# sensors_actuators_shieldv1_1.net
KiCad netlist of a schematic drawn in EAGLE
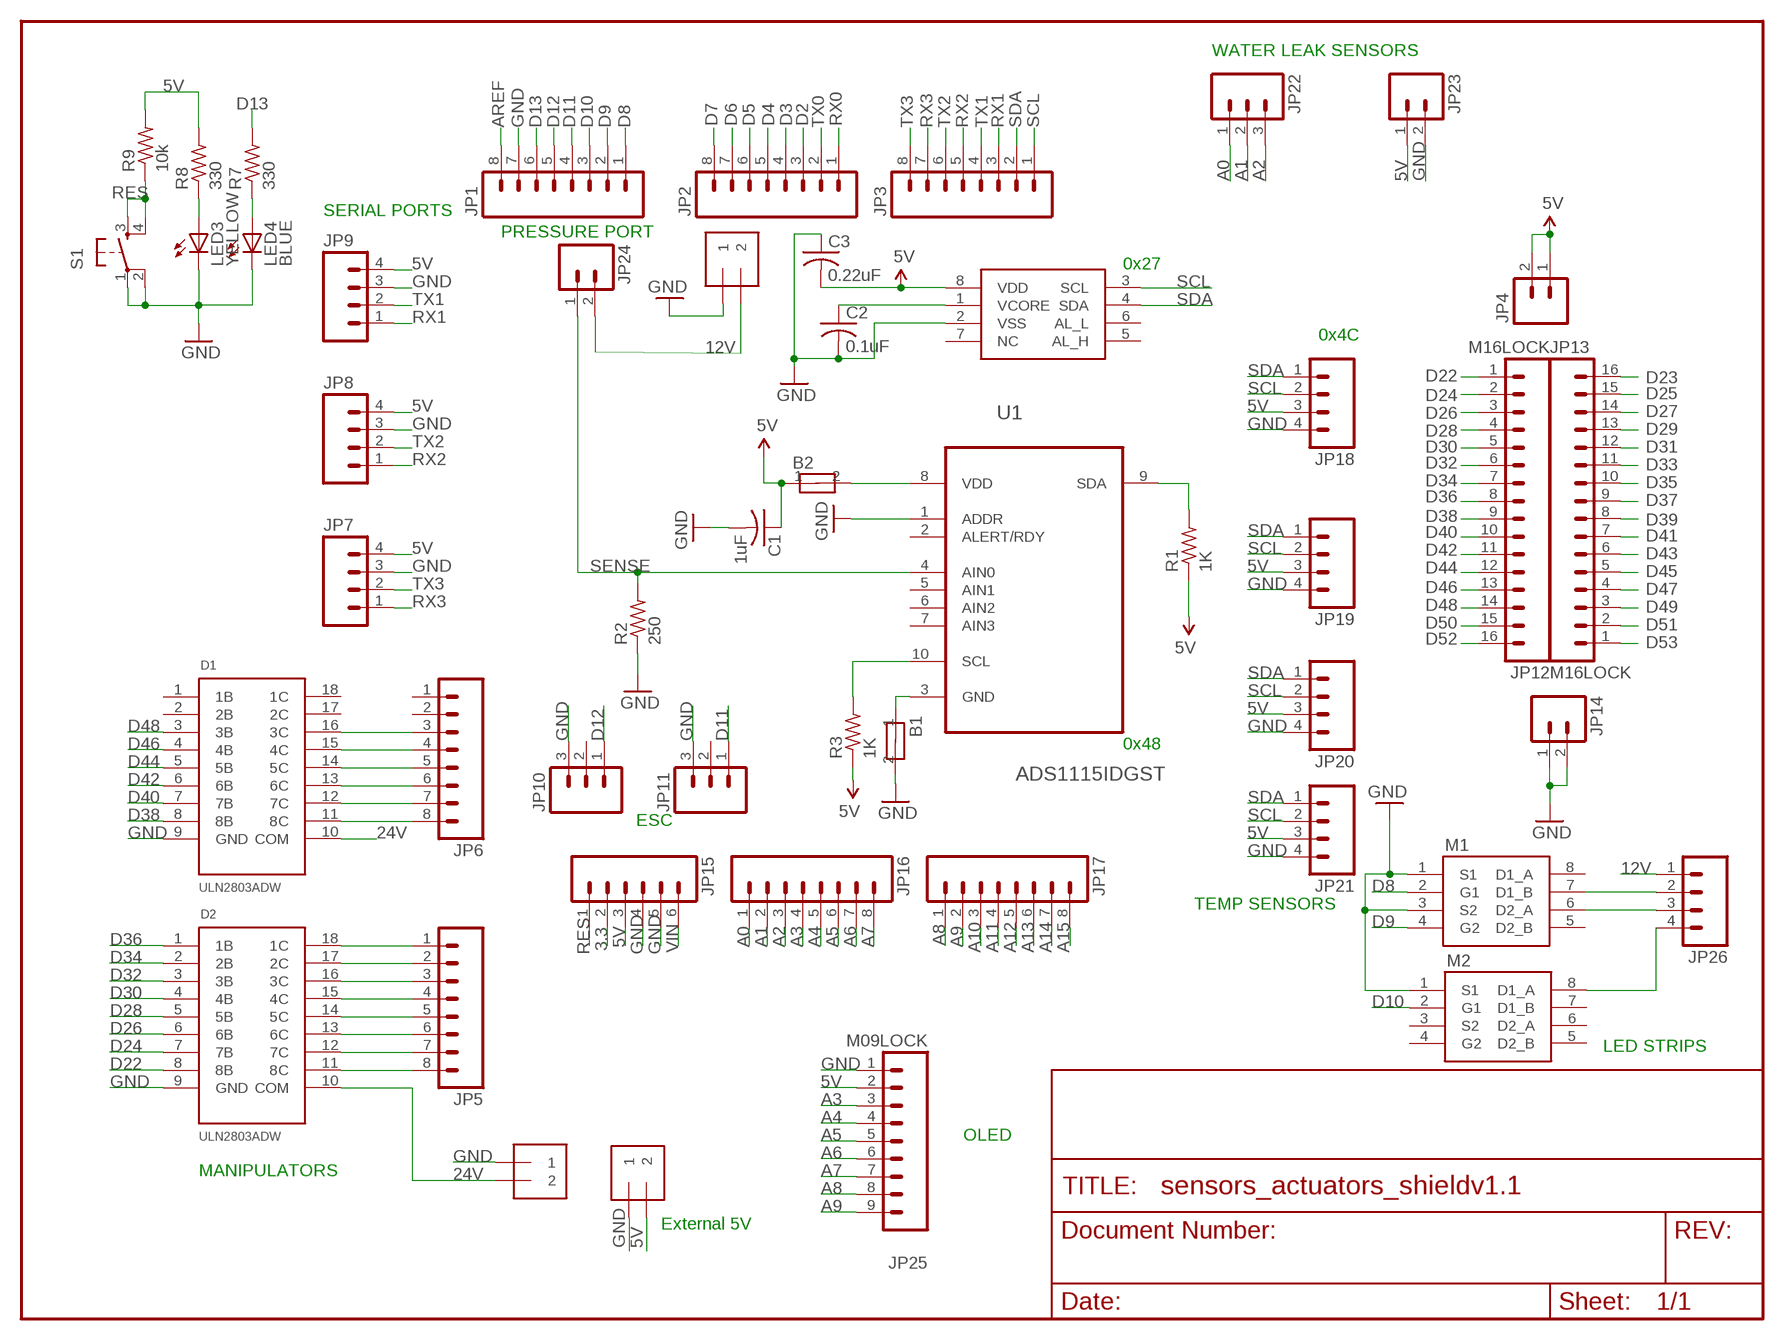
[diagram p0: schematic, sheet 1]

(export (version "E")
  (design (tool "Eeschema 10.0.6"))
  (components
    (comp (ref "B1")
      (value "MMZ2012Y152B0.4OHM,500MA")
      (footprint "eagle-import:0805")
      (fields (field (name "MPN") "MMZ2012Y152B"))
      (libsource (lib "eagle-import") (part "MMZ2012Y152B0.4OHM,500MA"))
    )
    (comp (ref "B2")
      (value "MMZ2012Y152B0.4OHM,500MA")
      (footprint "eagle-import:0805")
      (fields (field (name "MPN") "MMZ2012Y152B"))
      (libsource (lib "eagle-import") (part "MMZ2012Y152B0.4OHM,500MA"))
    )
    (comp (ref "C1")
      (value "1uF")
      (footprint "eagle-import:C0805")
      (fields (field (name "MF") "KEMET") (field (name "MPN") "C0805C105M4RACTU"))
      (libsource (lib "eagle-import") (part "C-USC0805"))
    )
    (comp (ref "C2")
      (value "0.1uF")
      (footprint "eagle-import:C0805")
      (fields (field (name "MPN") "08055C104K4Z2A"))
      (libsource (lib "eagle-import") (part "C-USC0805"))
    )
    (comp (ref "C3")
      (value "0.22uF")
      (footprint "eagle-import:C0805")
      (fields (field (name "MPN") "CGA4J2X8R1E224K125AA"))
      (libsource (lib "eagle-import") (part "C-USC0805"))
    )
    (comp (ref "D1")
      (value "ULN2803ADW")
      (footprint "eagle-import:SOIC")
      (fields (field (name "MF") "TEXAS INSTRUMENTS"))
      (libsource (lib "eagle-import") (part "ULN2803ADW"))
    )
    (comp (ref "D2")
      (value "ULN2803ADW")
      (footprint "eagle-import:SOIC")
      (fields (field (name "MF") "TEXAS INSTRUMENTS"))
      (libsource (lib "eagle-import") (part "ULN2803ADW"))
    )
    (comp (ref "J1")
      (value "1X2-3.5MM")
      (footprint "eagle-import:1X2-3.5MM")
      (fields (field (name "MPN") "691103110002"))
      (libsource (lib "eagle-import") (part "1X2-3.5MM"))
    )
    (comp (ref "J2")
      (value "1X2-3.5MM")
      (footprint "eagle-import:1X2-3.5MM")
      (fields (field (name "MPN") "691103110002"))
      (libsource (lib "eagle-import") (part "1X2-3.5MM"))
    )
    (comp (ref "J3")
      (value "1X2-3.5MM")
      (footprint "eagle-import:1X2-3.5MM")
      (fields (field (name "MPN") "691103110002"))
      (libsource (lib "eagle-import") (part "1X2-3.5MM"))
    )
    (comp (ref "JP1")
      (value "M08LOCK")
      (footprint "eagle-import:1X08_LOCK")
      (libsource (lib "eagle-import") (part "M08LOCK"))
    )
    (comp (ref "JP2")
      (value "M08LOCK")
      (footprint "eagle-import:1X08_LOCK")
      (libsource (lib "eagle-import") (part "M08LOCK"))
    )
    (comp (ref "JP3")
      (value "M08LOCK")
      (footprint "eagle-import:1X08_LOCK")
      (libsource (lib "eagle-import") (part "M08LOCK"))
    )
    (comp (ref "JP4")
      (value "M02LOCK")
      (footprint "eagle-import:1X02_LOCK")
      (libsource (lib "eagle-import") (part "M02LOCK"))
    )
    (comp (ref "JP5")
      (value "M08LOCK")
      (footprint "eagle-import:1X08_LOCK")
      (libsource (lib "eagle-import") (part "M08LOCK"))
    )
    (comp (ref "JP6")
      (value "M08LOCK")
      (footprint "eagle-import:1X08_LOCK")
      (libsource (lib "eagle-import") (part "M08LOCK"))
    )
    (comp (ref "JP7")
      (value "M04LOCK")
      (footprint "eagle-import:1X04_LOCK")
      (libsource (lib "eagle-import") (part "M04LOCK"))
    )
    (comp (ref "JP8")
      (value "M04LOCK")
      (footprint "eagle-import:1X04_LOCK")
      (libsource (lib "eagle-import") (part "M04LOCK"))
    )
    (comp (ref "JP9")
      (value "M04LOCK")
      (footprint "eagle-import:1X04_LOCK")
      (libsource (lib "eagle-import") (part "M04LOCK"))
    )
    (comp (ref "JP10")
      (value "M03LOCK")
      (footprint "eagle-import:1X03_LOCK")
      (libsource (lib "eagle-import") (part "M03LOCK"))
    )
    (comp (ref "JP11")
      (value "M03LOCK")
      (footprint "eagle-import:1X03_LOCK")
      (libsource (lib "eagle-import") (part "M03LOCK"))
    )
    (comp (ref "JP12")
      (value "M16LOCK")
      (footprint "eagle-import:1X16_LOCK")
      (libsource (lib "eagle-import") (part "M16LOCK"))
    )
    (comp (ref "JP13")
      (value "M16LOCK")
      (footprint "eagle-import:1X16_LOCK")
      (libsource (lib "eagle-import") (part "M16LOCK"))
    )
    (comp (ref "JP14")
      (value "M02LOCK")
      (footprint "eagle-import:1X02_LOCK")
      (libsource (lib "eagle-import") (part "M02LOCK"))
    )
    (comp (ref "JP15")
      (value "M06LOCK")
      (footprint "eagle-import:1X06_LOCK")
      (libsource (lib "eagle-import") (part "M06LOCK"))
    )
    (comp (ref "JP16")
      (value "M08LOCK")
      (footprint "eagle-import:1X08_LOCK")
      (libsource (lib "eagle-import") (part "M08LOCK"))
    )
    (comp (ref "JP17")
      (value "M08LOCK")
      (footprint "eagle-import:1X08_LOCK")
      (libsource (lib "eagle-import") (part "M08LOCK"))
    )
    (comp (ref "JP18")
      (value "M04LOCK")
      (footprint "eagle-import:1X04_LOCK")
      (libsource (lib "eagle-import") (part "M04LOCK"))
    )
    (comp (ref "JP19")
      (value "M04LOCK")
      (footprint "eagle-import:1X04_LOCK")
      (libsource (lib "eagle-import") (part "M04LOCK"))
    )
    (comp (ref "JP20")
      (value "M04LOCK")
      (footprint "eagle-import:1X04_LOCK")
      (libsource (lib "eagle-import") (part "M04LOCK"))
    )
    (comp (ref "JP21")
      (value "M04LOCK")
      (footprint "eagle-import:1X04_LOCK")
      (libsource (lib "eagle-import") (part "M04LOCK"))
    )
    (comp (ref "JP22")
      (value "M03LOCK")
      (footprint "eagle-import:1X03_LOCK")
      (libsource (lib "eagle-import") (part "M03LOCK"))
    )
    (comp (ref "JP23")
      (value "M02LOCK")
      (footprint "eagle-import:1X02_LOCK")
      (libsource (lib "eagle-import") (part "M02LOCK"))
    )
    (comp (ref "JP24")
      (value "M02LOCK")
      (footprint "eagle-import:1X02_LOCK")
      (libsource (lib "eagle-import") (part "M02LOCK"))
    )
    (comp (ref "JP25")
      (value "M09LOCK")
      (footprint "eagle-import:1X09_LOCK")
      (libsource (lib "eagle-import") (part "M09LOCK"))
    )
    (comp (ref "JP26")
      (value "M04LOCK")
      (footprint "eagle-import:1X04_LOCK")
      (libsource (lib "eagle-import") (part "M04LOCK"))
    )
    (comp (ref "LED3")
      (value "YELLOW")
      (footprint "eagle-import:CHIPLED_0805")
      (fields (field (name "MPN") "KP-2012SYCK-J3"))
      (libsource (lib "eagle-import") (part "LEDCHIPLED_0805"))
    )
    (comp (ref "LED4")
      (value "BLUE")
      (footprint "eagle-import:CHIPLED_0805")
      (fields (field (name "MPN") "150080BS75000"))
      (libsource (lib "eagle-import") (part "LEDCHIPLED_0805"))
    )
    (comp (ref "M1")
      (value "IRF7910PBF")
      (footprint "eagle-import:SO-8")
      (libsource (lib "eagle-import") (part "IRF7910PBF"))
    )
    (comp (ref "M2")
      (value "IRF7910PBF")
      (footprint "eagle-import:SO-8")
      (libsource (lib "eagle-import") (part "IRF7910PBF"))
    )
    (comp (ref "R1")
      (value "1K")
      (footprint "eagle-import:M0805")
      (fields (field (name "MF") "VISHAY/DALE") (field (name "MPN") "CRCW08051K00FKTA"))
      (libsource (lib "eagle-import") (part "R-US_M0805"))
    )
    (comp (ref "R2")
      (value "250")
      (footprint "eagle-import:M0805")
      (fields (field (name "MPN") "PLTT0805Z2500AGTS"))
      (libsource (lib "eagle-import") (part "R-US_M0805"))
    )
    (comp (ref "R3")
      (value "1K")
      (footprint "eagle-import:M0805")
      (fields (field (name "MF") "VISHAY/DALE") (field (name "MPN") "CRCW08051K00FKTA"))
      (libsource (lib "eagle-import") (part "R-US_M0805"))
    )
    (comp (ref "R7")
      (value "330")
      (footprint "eagle-import:M0805")
      (libsource (lib "eagle-import") (part "R-US_M0805"))
    )
    (comp (ref "R8")
      (value "330")
      (footprint "eagle-import:M0805")
      (libsource (lib "eagle-import") (part "R-US_M0805"))
    )
    (comp (ref "R9")
      (value "10k")
      (footprint "eagle-import:M0805")
      (fields (field (name "MPN") "MCTF0805DTC1002"))
      (libsource (lib "eagle-import") (part "R-US_M0805"))
    )
    (comp (ref "S1")
      (value "TAC_SWITCHPTH")
      (footprint "eagle-import:TACTILE-PTH")
      (libsource (lib "eagle-import") (part "TAC_SWITCHPTH"))
    )
    (comp (ref "U$2")
      (value "HIH6130")
      (footprint "eagle-import:SO-8")
      (fields (field (name "MPN") "HIH6131-021-001"))
      (libsource (lib "eagle-import") (part "HIH6130"))
    )
    (comp (ref "U1")
      (value "ADS1115IDGST")
      (footprint "eagle-import:SOP50P490X110-10N")
      (libsource (lib "eagle-import") (part "ADS1115IDGST"))
    )
  )
  (nets
    (net (code "1") (name "/3.3") (class "Default")
      (node (ref "JP15") (pin "2") (pinfunction "2_2") (pintype "passive"))
    )
    (net (code "2") (name "/12V") (class "Default")
      (node (ref "J1") (pin "2") (pinfunction "2_2") (pintype "passive"))
      (node (ref "JP24") (pin "2") (pinfunction "2_2") (pintype "passive"))
      (node (ref "JP26") (pin "1") (pinfunction "1_1") (pintype "passive"))
    )
    (net (code "3") (name "/24V") (class "Default")
      (node (ref "D1") (pin "10") (pinfunction "COM_10") (pintype "bidirectional"))
      (node (ref "D2") (pin "10") (pinfunction "COM_10") (pintype "bidirectional"))
      (node (ref "J2") (pin "2") (pinfunction "2_2") (pintype "passive"))
    )
    (net (code "4") (name "/A0") (class "Default")
      (node (ref "JP16") (pin "1") (pinfunction "1_1") (pintype "passive"))
      (node (ref "JP22") (pin "1") (pinfunction "1_1") (pintype "passive"))
    )
    (net (code "5") (name "/A1") (class "Default")
      (node (ref "JP16") (pin "2") (pinfunction "2_2") (pintype "passive"))
      (node (ref "JP22") (pin "2") (pinfunction "2_2") (pintype "passive"))
    )
    (net (code "6") (name "/A2") (class "Default")
      (node (ref "JP16") (pin "3") (pinfunction "3_3") (pintype "passive"))
      (node (ref "JP22") (pin "3") (pinfunction "3_3") (pintype "passive"))
    )
    (net (code "7") (name "/A3") (class "Default")
      (node (ref "JP16") (pin "4") (pinfunction "4_4") (pintype "passive"))
      (node (ref "JP25") (pin "3") (pinfunction "3_3") (pintype "passive"))
    )
    (net (code "8") (name "/A4") (class "Default")
      (node (ref "JP16") (pin "5") (pinfunction "5_5") (pintype "passive"))
      (node (ref "JP25") (pin "4") (pinfunction "4_4") (pintype "passive"))
    )
    (net (code "9") (name "/A5") (class "Default")
      (node (ref "JP16") (pin "6") (pinfunction "6_6") (pintype "passive"))
      (node (ref "JP25") (pin "5") (pinfunction "5_5") (pintype "passive"))
    )
    (net (code "10") (name "/A6") (class "Default")
      (node (ref "JP16") (pin "7") (pinfunction "7_7") (pintype "passive"))
      (node (ref "JP25") (pin "6") (pinfunction "6_6") (pintype "passive"))
    )
    (net (code "11") (name "/A7") (class "Default")
      (node (ref "JP16") (pin "8") (pinfunction "8_8") (pintype "passive"))
      (node (ref "JP25") (pin "7") (pinfunction "7_7") (pintype "passive"))
    )
    (net (code "12") (name "/A8") (class "Default")
      (node (ref "JP17") (pin "1") (pinfunction "1_1") (pintype "passive"))
      (node (ref "JP25") (pin "8") (pinfunction "8_8") (pintype "passive"))
    )
    (net (code "13") (name "/A9") (class "Default")
      (node (ref "JP17") (pin "2") (pinfunction "2_2") (pintype "passive"))
      (node (ref "JP25") (pin "9") (pinfunction "9_9") (pintype "passive"))
    )
    (net (code "14") (name "/A10") (class "Default")
      (node (ref "JP17") (pin "3") (pinfunction "3_3") (pintype "passive"))
    )
    (net (code "15") (name "/A11") (class "Default")
      (node (ref "JP17") (pin "4") (pinfunction "4_4") (pintype "passive"))
    )
    (net (code "16") (name "/A12") (class "Default")
      (node (ref "JP17") (pin "5") (pinfunction "5_5") (pintype "passive"))
    )
    (net (code "17") (name "/A13") (class "Default")
      (node (ref "JP17") (pin "6") (pinfunction "6_6") (pintype "passive"))
    )
    (net (code "18") (name "/A14") (class "Default")
      (node (ref "JP17") (pin "7") (pinfunction "7_7") (pintype "passive"))
    )
    (net (code "19") (name "/A15") (class "Default")
      (node (ref "JP17") (pin "8") (pinfunction "8_8") (pintype "passive"))
    )
    (net (code "20") (name "/AREF") (class "Default")
      (node (ref "JP1") (pin "8") (pinfunction "8_8") (pintype "passive"))
    )
    (net (code "21") (name "/D2") (class "Default")
      (node (ref "JP2") (pin "3") (pinfunction "3_3") (pintype "passive"))
    )
    (net (code "22") (name "/D3") (class "Default")
      (node (ref "JP2") (pin "4") (pinfunction "4_4") (pintype "passive"))
    )
    (net (code "23") (name "/D4") (class "Default")
      (node (ref "JP2") (pin "5") (pinfunction "5_5") (pintype "passive"))
    )
    (net (code "24") (name "/D5") (class "Default")
      (node (ref "JP2") (pin "6") (pinfunction "6_6") (pintype "passive"))
    )
    (net (code "25") (name "/D6") (class "Default")
      (node (ref "JP2") (pin "7") (pinfunction "7_7") (pintype "passive"))
    )
    (net (code "26") (name "/D7") (class "Default")
      (node (ref "JP2") (pin "8") (pinfunction "8_8") (pintype "passive"))
    )
    (net (code "27") (name "/D8") (class "Default")
      (node (ref "JP1") (pin "1") (pinfunction "1_1") (pintype "passive"))
      (node (ref "M1") (pin "2") (pinfunction "G1_2") (pintype "bidirectional"))
    )
    (net (code "28") (name "/D9") (class "Default")
      (node (ref "JP1") (pin "2") (pinfunction "2_2") (pintype "passive"))
      (node (ref "M1") (pin "4") (pinfunction "G2_4") (pintype "bidirectional"))
    )
    (net (code "29") (name "/D10") (class "Default")
      (node (ref "JP1") (pin "3") (pinfunction "3_3") (pintype "passive"))
      (node (ref "M2") (pin "2") (pinfunction "G1_2") (pintype "bidirectional"))
    )
    (net (code "30") (name "/D11") (class "Default")
      (node (ref "JP1") (pin "4") (pinfunction "4_4") (pintype "passive"))
      (node (ref "JP11") (pin "1") (pinfunction "1_1") (pintype "passive"))
    )
    (net (code "31") (name "/D12") (class "Default")
      (node (ref "JP1") (pin "5") (pinfunction "5_5") (pintype "passive"))
      (node (ref "JP10") (pin "1") (pinfunction "1_1") (pintype "passive"))
    )
    (net (code "32") (name "/D13") (class "Default")
      (node (ref "JP1") (pin "6") (pinfunction "6_6") (pintype "passive"))
      (node (ref "R7") (pin "2") (pinfunction "2_2") (pintype "passive"))
    )
    (net (code "33") (name "/D22") (class "Default")
      (node (ref "D2") (pin "8") (pinfunction "8B_8") (pintype "bidirectional"))
      (node (ref "JP12") (pin "1") (pinfunction "1_1") (pintype "passive"))
    )
    (net (code "34") (name "/D23") (class "Default")
      (node (ref "JP13") (pin "16") (pinfunction "16_16") (pintype "passive"))
    )
    (net (code "35") (name "/D24") (class "Default")
      (node (ref "D2") (pin "7") (pinfunction "7B_7") (pintype "bidirectional"))
      (node (ref "JP12") (pin "2") (pinfunction "2_2") (pintype "passive"))
    )
    (net (code "36") (name "/D25") (class "Default")
      (node (ref "JP13") (pin "15") (pinfunction "15_15") (pintype "passive"))
    )
    (net (code "37") (name "/D26") (class "Default")
      (node (ref "D2") (pin "6") (pinfunction "6B_6") (pintype "bidirectional"))
      (node (ref "JP12") (pin "3") (pinfunction "3_3") (pintype "passive"))
    )
    (net (code "38") (name "/D27") (class "Default")
      (node (ref "JP13") (pin "14") (pinfunction "14_14") (pintype "passive"))
    )
    (net (code "39") (name "/D28") (class "Default")
      (node (ref "D2") (pin "5") (pinfunction "5B_5") (pintype "bidirectional"))
      (node (ref "JP12") (pin "4") (pinfunction "4_4") (pintype "passive"))
    )
    (net (code "40") (name "/D29") (class "Default")
      (node (ref "JP13") (pin "13") (pinfunction "13_13") (pintype "passive"))
    )
    (net (code "41") (name "/D30") (class "Default")
      (node (ref "D2") (pin "4") (pinfunction "4B_4") (pintype "bidirectional"))
      (node (ref "JP12") (pin "5") (pinfunction "5_5") (pintype "passive"))
    )
    (net (code "42") (name "/D31") (class "Default")
      (node (ref "JP13") (pin "12") (pinfunction "12_12") (pintype "passive"))
    )
    (net (code "43") (name "/D32") (class "Default")
      (node (ref "D2") (pin "3") (pinfunction "3B_3") (pintype "bidirectional"))
      (node (ref "JP12") (pin "6") (pinfunction "6_6") (pintype "passive"))
    )
    (net (code "44") (name "/D33") (class "Default")
      (node (ref "JP13") (pin "11") (pinfunction "11_11") (pintype "passive"))
    )
    (net (code "45") (name "/D34") (class "Default")
      (node (ref "D2") (pin "2") (pinfunction "2B_2") (pintype "bidirectional"))
      (node (ref "JP12") (pin "7") (pinfunction "7_7") (pintype "passive"))
    )
    (net (code "46") (name "/D35") (class "Default")
      (node (ref "JP13") (pin "10") (pinfunction "10_10") (pintype "passive"))
    )
    (net (code "47") (name "/D36") (class "Default")
      (node (ref "D2") (pin "1") (pinfunction "1B_1") (pintype "bidirectional"))
      (node (ref "JP12") (pin "8") (pinfunction "8_8") (pintype "passive"))
    )
    (net (code "48") (name "/D37") (class "Default")
      (node (ref "JP13") (pin "9") (pinfunction "9_9") (pintype "passive"))
    )
    (net (code "49") (name "/D38") (class "Default")
      (node (ref "D1") (pin "8") (pinfunction "8B_8") (pintype "bidirectional"))
      (node (ref "JP12") (pin "9") (pinfunction "9_9") (pintype "passive"))
    )
    (net (code "50") (name "/D39") (class "Default")
      (node (ref "JP13") (pin "8") (pinfunction "8_8") (pintype "passive"))
    )
    (net (code "51") (name "/D40") (class "Default")
      (node (ref "D1") (pin "7") (pinfunction "7B_7") (pintype "bidirectional"))
      (node (ref "JP12") (pin "10") (pinfunction "10_10") (pintype "passive"))
    )
    (net (code "52") (name "/D41") (class "Default")
      (node (ref "JP13") (pin "7") (pinfunction "7_7") (pintype "passive"))
    )
    (net (code "53") (name "/D42") (class "Default")
      (node (ref "D1") (pin "6") (pinfunction "6B_6") (pintype "bidirectional"))
      (node (ref "JP12") (pin "11") (pinfunction "11_11") (pintype "passive"))
    )
    (net (code "54") (name "/D43") (class "Default")
      (node (ref "JP13") (pin "6") (pinfunction "6_6") (pintype "passive"))
    )
    (net (code "55") (name "/D44") (class "Default")
      (node (ref "D1") (pin "5") (pinfunction "5B_5") (pintype "bidirectional"))
      (node (ref "JP12") (pin "12") (pinfunction "12_12") (pintype "passive"))
    )
    (net (code "56") (name "/D45") (class "Default")
      (node (ref "JP13") (pin "5") (pinfunction "5_5") (pintype "passive"))
    )
    (net (code "57") (name "/D46") (class "Default")
      (node (ref "D1") (pin "4") (pinfunction "4B_4") (pintype "bidirectional"))
      (node (ref "JP12") (pin "13") (pinfunction "13_13") (pintype "passive"))
    )
    (net (code "58") (name "/D47") (class "Default")
      (node (ref "JP13") (pin "4") (pinfunction "4_4") (pintype "passive"))
    )
    (net (code "59") (name "/D48") (class "Default")
      (node (ref "D1") (pin "3") (pinfunction "3B_3") (pintype "bidirectional"))
      (node (ref "JP12") (pin "14") (pinfunction "14_14") (pintype "passive"))
    )
    (net (code "60") (name "/D49") (class "Default")
      (node (ref "JP13") (pin "3") (pinfunction "3_3") (pintype "passive"))
    )
    (net (code "61") (name "/D50") (class "Default")
      (node (ref "JP12") (pin "15") (pinfunction "15_15") (pintype "passive"))
    )
    (net (code "62") (name "/D51") (class "Default")
      (node (ref "JP13") (pin "2") (pinfunction "2_2") (pintype "passive"))
    )
    (net (code "63") (name "/D52") (class "Default")
      (node (ref "JP12") (pin "16") (pinfunction "16_16") (pintype "passive"))
    )
    (net (code "64") (name "/D53") (class "Default")
      (node (ref "JP13") (pin "1") (pinfunction "1_1") (pintype "passive"))
    )
    (net (code "65") (name "/RES") (class "Default")
      (node (ref "JP15") (pin "1") (pinfunction "1_1") (pintype "passive"))
      (node (ref "R9") (pin "1") (pinfunction "1_1") (pintype "passive"))
      (node (ref "S1") (pin "3") (pinfunction "3_3") (pintype "passive"))
      (node (ref "S1") (pin "4") (pinfunction "4_4") (pintype "passive"))
    )
    (net (code "66") (name "/RX0") (class "Default")
      (node (ref "JP2") (pin "1") (pinfunction "1_1") (pintype "passive"))
    )
    (net (code "67") (name "/RX1") (class "Default")
      (node (ref "JP3") (pin "3") (pinfunction "3_3") (pintype "passive"))
      (node (ref "JP9") (pin "1") (pinfunction "1_1") (pintype "passive"))
    )
    (net (code "68") (name "/RX2") (class "Default")
      (node (ref "JP3") (pin "5") (pinfunction "5_5") (pintype "passive"))
      (node (ref "JP8") (pin "1") (pinfunction "1_1") (pintype "passive"))
    )
    (net (code "69") (name "/RX3") (class "Default")
      (node (ref "JP3") (pin "7") (pinfunction "7_7") (pintype "passive"))
      (node (ref "JP7") (pin "1") (pinfunction "1_1") (pintype "passive"))
    )
    (net (code "70") (name "/SCL") (class "Default")
      (node (ref "JP18") (pin "2") (pinfunction "2_2") (pintype "passive"))
      (node (ref "JP19") (pin "2") (pinfunction "2_2") (pintype "passive"))
      (node (ref "JP20") (pin "2") (pinfunction "2_2") (pintype "passive"))
      (node (ref "JP21") (pin "2") (pinfunction "2_2") (pintype "passive"))
      (node (ref "JP3") (pin "1") (pinfunction "1_1") (pintype "passive"))
      (node (ref "U$2") (pin "3") (pinfunction "SCL_3") (pintype "bidirectional"))
    )
    (net (code "71") (name "/SDA") (class "Default")
      (node (ref "JP18") (pin "1") (pinfunction "1_1") (pintype "passive"))
      (node (ref "JP19") (pin "1") (pinfunction "1_1") (pintype "passive"))
      (node (ref "JP20") (pin "1") (pinfunction "1_1") (pintype "passive"))
      (node (ref "JP21") (pin "1") (pinfunction "1_1") (pintype "passive"))
      (node (ref "JP3") (pin "2") (pinfunction "2_2") (pintype "passive"))
      (node (ref "U$2") (pin "4") (pinfunction "SDA_4") (pintype "bidirectional"))
    )
    (net (code "72") (name "/SENSE") (class "Default")
      (node (ref "JP24") (pin "1") (pinfunction "1_1") (pintype "passive"))
      (node (ref "R2") (pin "2") (pinfunction "2_2") (pintype "passive"))
      (node (ref "U1") (pin "4") (pinfunction "AIN0_4") (pintype "input"))
    )
    (net (code "73") (name "/TX0") (class "Default")
      (node (ref "JP2") (pin "2") (pinfunction "2_2") (pintype "passive"))
    )
    (net (code "74") (name "/TX1") (class "Default")
      (node (ref "JP3") (pin "4") (pinfunction "4_4") (pintype "passive"))
      (node (ref "JP9") (pin "2") (pinfunction "2_2") (pintype "passive"))
    )
    (net (code "75") (name "/TX2") (class "Default")
      (node (ref "JP3") (pin "6") (pinfunction "6_6") (pintype "passive"))
      (node (ref "JP8") (pin "2") (pinfunction "2_2") (pintype "passive"))
    )
    (net (code "76") (name "/TX3") (class "Default")
      (node (ref "JP3") (pin "8") (pinfunction "8_8") (pintype "passive"))
      (node (ref "JP7") (pin "2") (pinfunction "2_2") (pintype "passive"))
    )
    (net (code "77") (name "/VIN") (class "Default")
      (node (ref "JP15") (pin "6") (pinfunction "6_6") (pintype "passive"))
    )
    (net (code "78") (name "5V") (class "Default")
      (node (ref "B2") (pin "1") (pinfunction "1_1") (pintype "passive"))
      (node (ref "C1") (pin "1") (pinfunction "1_1") (pintype "passive"))
      (node (ref "C3") (pin "2") (pinfunction "2_2") (pintype "passive"))
      (node (ref "J3") (pin "2") (pinfunction "2_2") (pintype "passive"))
      (node (ref "JP15") (pin "3") (pinfunction "3_3") (pintype "passive"))
      (node (ref "JP18") (pin "3") (pinfunction "3_3") (pintype "passive"))
      (node (ref "JP19") (pin "3") (pinfunction "3_3") (pintype "passive"))
      (node (ref "JP20") (pin "3") (pinfunction "3_3") (pintype "passive"))
      (node (ref "JP21") (pin "3") (pinfunction "3_3") (pintype "passive"))
      (node (ref "JP23") (pin "1") (pinfunction "1_1") (pintype "passive"))
      (node (ref "JP25") (pin "2") (pinfunction "2_2") (pintype "passive"))
      (node (ref "JP4") (pin "1") (pinfunction "1_1") (pintype "passive"))
      (node (ref "JP4") (pin "2") (pinfunction "2_2") (pintype "passive"))
      (node (ref "JP7") (pin "4") (pinfunction "4_4") (pintype "passive"))
      (node (ref "JP8") (pin "4") (pinfunction "4_4") (pintype "passive"))
      (node (ref "JP9") (pin "4") (pinfunction "4_4") (pintype "passive"))
      (node (ref "R1") (pin "1") (pinfunction "1_1") (pintype "passive"))
      (node (ref "R3") (pin "1") (pinfunction "1_1") (pintype "passive"))
      (node (ref "R8") (pin "2") (pinfunction "2_2") (pintype "passive"))
      (node (ref "R9") (pin "2") (pinfunction "2_2") (pintype "passive"))
      (node (ref "U$2") (pin "8") (pinfunction "VDD_8") (pintype "bidirectional"))
    )
    (net (code "79") (name "GND") (class "Default")
      (node (ref "B1") (pin "2") (pinfunction "2_2") (pintype "passive"))
      (node (ref "C1") (pin "2") (pinfunction "2_2") (pintype "passive"))
      (node (ref "C2") (pin "2") (pinfunction "2_2") (pintype "passive"))
      (node (ref "C3") (pin "1") (pinfunction "1_1") (pintype "passive"))
      (node (ref "D1") (pin "9") (pinfunction "GND_9") (pintype "bidirectional"))
      (node (ref "D2") (pin "9") (pinfunction "GND_9") (pintype "bidirectional"))
      (node (ref "J1") (pin "1") (pinfunction "1_1") (pintype "passive"))
      (node (ref "J2") (pin "1") (pinfunction "1_1") (pintype "passive"))
      (node (ref "J3") (pin "1") (pinfunction "1_1") (pintype "passive"))
      (node (ref "JP1") (pin "7") (pinfunction "7_7") (pintype "passive"))
      (node (ref "JP10") (pin "3") (pinfunction "3_3") (pintype "passive"))
      (node (ref "JP11") (pin "3") (pinfunction "3_3") (pintype "passive"))
      (node (ref "JP14") (pin "1") (pinfunction "1_1") (pintype "passive"))
      (node (ref "JP14") (pin "2") (pinfunction "2_2") (pintype "passive"))
      (node (ref "JP15") (pin "4") (pinfunction "4_4") (pintype "passive"))
      (node (ref "JP15") (pin "5") (pinfunction "5_5") (pintype "passive"))
      (node (ref "JP18") (pin "4") (pinfunction "4_4") (pintype "passive"))
      (node (ref "JP19") (pin "4") (pinfunction "4_4") (pintype "passive"))
      (node (ref "JP20") (pin "4") (pinfunction "4_4") (pintype "passive"))
      (node (ref "JP21") (pin "4") (pinfunction "4_4") (pintype "passive"))
      (node (ref "JP23") (pin "2") (pinfunction "2_2") (pintype "passive"))
      (node (ref "JP25") (pin "1") (pinfunction "1_1") (pintype "passive"))
      (node (ref "JP7") (pin "3") (pinfunction "3_3") (pintype "passive"))
      (node (ref "JP8") (pin "3") (pinfunction "3_3") (pintype "passive"))
      (node (ref "JP9") (pin "3") (pinfunction "3_3") (pintype "passive"))
      (node (ref "LED3") (pin "C") (pinfunction "C_C") (pintype "passive"))
      (node (ref "LED4") (pin "C") (pinfunction "C_C") (pintype "passive"))
      (node (ref "M1") (pin "1") (pinfunction "S1_1") (pintype "bidirectional"))
      (node (ref "M1") (pin "3") (pinfunction "S2_3") (pintype "bidirectional"))
      (node (ref "M2") (pin "1") (pinfunction "S1_1") (pintype "bidirectional"))
      (node (ref "R2") (pin "1") (pinfunction "1_1") (pintype "passive"))
      (node (ref "S1") (pin "1") (pinfunction "1_1") (pintype "passive"))
      (node (ref "S1") (pin "2") (pinfunction "2_2") (pintype "passive"))
      (node (ref "U$2") (pin "2") (pinfunction "VSS_2") (pintype "bidirectional"))
      (node (ref "U1") (pin "1") (pinfunction "ADDR_1") (pintype "input"))
    )
    (net (code "80") (name "Net-(D1-3C)") (class "Default")
      (node (ref "D1") (pin "16") (pinfunction "3C_16") (pintype "bidirectional"))
      (node (ref "JP6") (pin "3") (pinfunction "3_3") (pintype "passive"))
    )
    (net (code "81") (name "Net-(D1-4C)") (class "Default")
      (node (ref "D1") (pin "15") (pinfunction "4C_15") (pintype "bidirectional"))
      (node (ref "JP6") (pin "4") (pinfunction "4_4") (pintype "passive"))
    )
    (net (code "82") (name "Net-(D1-5C)") (class "Default")
      (node (ref "D1") (pin "14") (pinfunction "5C_14") (pintype "bidirectional"))
      (node (ref "JP6") (pin "5") (pinfunction "5_5") (pintype "passive"))
    )
    (net (code "83") (name "Net-(D1-6C)") (class "Default")
      (node (ref "D1") (pin "13") (pinfunction "6C_13") (pintype "bidirectional"))
      (node (ref "JP6") (pin "6") (pinfunction "6_6") (pintype "passive"))
    )
    (net (code "84") (name "Net-(D1-7C)") (class "Default")
      (node (ref "D1") (pin "12") (pinfunction "7C_12") (pintype "bidirectional"))
      (node (ref "JP6") (pin "7") (pinfunction "7_7") (pintype "passive"))
    )
    (net (code "85") (name "Net-(D1-8C)") (class "Default")
      (node (ref "D1") (pin "11") (pinfunction "8C_11") (pintype "bidirectional"))
      (node (ref "JP6") (pin "8") (pinfunction "8_8") (pintype "passive"))
    )
    (net (code "86") (name "Net-(D2-1C)") (class "Default")
      (node (ref "D2") (pin "18") (pinfunction "1C_18") (pintype "bidirectional"))
      (node (ref "JP5") (pin "1") (pinfunction "1_1") (pintype "passive"))
    )
    (net (code "87") (name "Net-(D2-2C)") (class "Default")
      (node (ref "D2") (pin "17") (pinfunction "2C_17") (pintype "bidirectional"))
      (node (ref "JP5") (pin "2") (pinfunction "2_2") (pintype "passive"))
    )
    (net (code "88") (name "Net-(D2-3C)") (class "Default")
      (node (ref "D2") (pin "16") (pinfunction "3C_16") (pintype "bidirectional"))
      (node (ref "JP5") (pin "3") (pinfunction "3_3") (pintype "passive"))
    )
    (net (code "89") (name "Net-(D2-4C)") (class "Default")
      (node (ref "D2") (pin "15") (pinfunction "4C_15") (pintype "bidirectional"))
      (node (ref "JP5") (pin "4") (pinfunction "4_4") (pintype "passive"))
    )
    (net (code "90") (name "Net-(D2-5C)") (class "Default")
      (node (ref "D2") (pin "14") (pinfunction "5C_14") (pintype "bidirectional"))
      (node (ref "JP5") (pin "5") (pinfunction "5_5") (pintype "passive"))
    )
    (net (code "91") (name "Net-(D2-6C)") (class "Default")
      (node (ref "D2") (pin "13") (pinfunction "6C_13") (pintype "bidirectional"))
      (node (ref "JP5") (pin "6") (pinfunction "6_6") (pintype "passive"))
    )
    (net (code "92") (name "Net-(D2-7C)") (class "Default")
      (node (ref "D2") (pin "12") (pinfunction "7C_12") (pintype "bidirectional"))
      (node (ref "JP5") (pin "7") (pinfunction "7_7") (pintype "passive"))
    )
    (net (code "93") (name "Net-(D2-8C)") (class "Default")
      (node (ref "D2") (pin "11") (pinfunction "8C_11") (pintype "bidirectional"))
      (node (ref "JP5") (pin "8") (pinfunction "8_8") (pintype "passive"))
    )
    (net (code "94") (name "Net-(LED3-PadA)") (class "Default")
      (node (ref "LED3") (pin "A") (pinfunction "A_A") (pintype "passive"))
      (node (ref "R8") (pin "1") (pinfunction "1_1") (pintype "passive"))
    )
    (net (code "95") (name "Net-(LED4-PadA)") (class "Default")
      (node (ref "LED4") (pin "A") (pinfunction "A_A") (pintype "passive"))
      (node (ref "R7") (pin "1") (pinfunction "1_1") (pintype "passive"))
    )
    (net (code "96") (name "Net-(M1-D1_B)") (class "Default")
      (node (ref "JP26") (pin "2") (pinfunction "2_2") (pintype "passive"))
      (node (ref "M1") (pin "7") (pinfunction "D1_B_7") (pintype "bidirectional"))
    )
    (net (code "97") (name "Net-(M1-D2_A)") (class "Default")
      (node (ref "JP26") (pin "3") (pinfunction "3_3") (pintype "passive"))
      (node (ref "M1") (pin "6") (pinfunction "D2_A_6") (pintype "bidirectional"))
    )
    (net (code "98") (name "Net-(M2-D1_A)") (class "Default")
      (node (ref "JP26") (pin "4") (pinfunction "4_4") (pintype "passive"))
      (node (ref "M2") (pin "8") (pinfunction "D1_A_8") (pintype "bidirectional"))
    )
    (net (code "99") (name "Net-(U$2-VCORE)") (class "Default")
      (node (ref "C2") (pin "1") (pinfunction "1_1") (pintype "passive"))
      (node (ref "U$2") (pin "1") (pinfunction "VCORE_1") (pintype "bidirectional"))
    )
    (net (code "100") (name "Net-(U1-GND)") (class "Default")
      (node (ref "B1") (pin "1") (pinfunction "1_1") (pintype "passive"))
      (node (ref "U1") (pin "3") (pinfunction "GND_3") (pintype "passive"))
    )
    (net (code "101") (name "Net-(U1-SCL)") (class "Default")
      (node (ref "R3") (pin "2") (pinfunction "2_2") (pintype "passive"))
      (node (ref "U1") (pin "10") (pinfunction "SCL_10") (pintype "input"))
    )
    (net (code "102") (name "Net-(U1-SDA)") (class "Default")
      (node (ref "R1") (pin "2") (pinfunction "2_2") (pintype "passive"))
      (node (ref "U1") (pin "9") (pinfunction "SDA_9") (pintype "bidirectional"))
    )
    (net (code "103") (name "Net-(U1-VDD)") (class "Default")
      (node (ref "B2") (pin "2") (pinfunction "2_2") (pintype "passive"))
      (node (ref "U1") (pin "8") (pinfunction "VDD_8") (pintype "power_in"))
    )
    (net (code "104") (name "unconnected-(D1-1B-Pad1)") (class "Default")
      (node (ref "D1") (pin "1") (pinfunction "1B_1") (pintype "bidirectional"))
    )
    (net (code "105") (name "unconnected-(D1-1C-Pad18)") (class "Default")
      (node (ref "D1") (pin "18") (pinfunction "1C_18") (pintype "bidirectional"))
    )
    (net (code "106") (name "unconnected-(D1-2B-Pad2)") (class "Default")
      (node (ref "D1") (pin "2") (pinfunction "2B_2") (pintype "bidirectional"))
    )
    (net (code "107") (name "unconnected-(D1-2C-Pad17)") (class "Default")
      (node (ref "D1") (pin "17") (pinfunction "2C_17") (pintype "bidirectional"))
    )
    (net (code "108") (name "unconnected-(JP6-Pad1)") (class "Default")
      (node (ref "JP6") (pin "1") (pinfunction "1_1") (pintype "passive"))
    )
    (net (code "109") (name "unconnected-(JP6-Pad2)") (class "Default")
      (node (ref "JP6") (pin "2") (pinfunction "2_2") (pintype "passive"))
    )
    (net (code "110") (name "unconnected-(JP10-Pad2)") (class "Default")
      (node (ref "JP10") (pin "2") (pinfunction "2_2") (pintype "passive"))
    )
    (net (code "111") (name "unconnected-(JP11-Pad2)") (class "Default")
      (node (ref "JP11") (pin "2") (pinfunction "2_2") (pintype "passive"))
    )
    (net (code "112") (name "unconnected-(M1-D1_A-Pad8)") (class "Default")
      (node (ref "M1") (pin "8") (pinfunction "D1_A_8") (pintype "bidirectional"))
    )
    (net (code "113") (name "unconnected-(M1-D2_B-Pad5)") (class "Default")
      (node (ref "M1") (pin "5") (pinfunction "D2_B_5") (pintype "bidirectional"))
    )
    (net (code "114") (name "unconnected-(M2-D1_B-Pad7)") (class "Default")
      (node (ref "M2") (pin "7") (pinfunction "D1_B_7") (pintype "bidirectional"))
    )
    (net (code "115") (name "unconnected-(M2-D2_A-Pad6)") (class "Default")
      (node (ref "M2") (pin "6") (pinfunction "D2_A_6") (pintype "bidirectional"))
    )
    (net (code "116") (name "unconnected-(M2-D2_B-Pad5)") (class "Default")
      (node (ref "M2") (pin "5") (pinfunction "D2_B_5") (pintype "bidirectional"))
    )
    (net (code "117") (name "unconnected-(M2-G2-Pad4)") (class "Default")
      (node (ref "M2") (pin "4") (pinfunction "G2_4") (pintype "bidirectional"))
    )
    (net (code "118") (name "unconnected-(M2-S2-Pad3)") (class "Default")
      (node (ref "M2") (pin "3") (pinfunction "S2_3") (pintype "bidirectional"))
    )
    (net (code "119") (name "unconnected-(U$2-AL_H-Pad5)") (class "Default")
      (node (ref "U$2") (pin "5") (pinfunction "AL_H_5") (pintype "bidirectional"))
    )
    (net (code "120") (name "unconnected-(U$2-AL_L-Pad6)") (class "Default")
      (node (ref "U$2") (pin "6") (pinfunction "AL_L_6") (pintype "bidirectional"))
    )
    (net (code "121") (name "unconnected-(U$2-NC-Pad7)") (class "Default")
      (node (ref "U$2") (pin "7") (pinfunction "NC_7") (pintype "bidirectional"))
    )
    (net (code "122") (name "unconnected-(U1-AIN1-Pad5)") (class "Default")
      (node (ref "U1") (pin "5") (pinfunction "AIN1_5") (pintype "input"))
    )
    (net (code "123") (name "unconnected-(U1-AIN2-Pad6)") (class "Default")
      (node (ref "U1") (pin "6") (pinfunction "AIN2_6") (pintype "input"))
    )
    (net (code "124") (name "unconnected-(U1-AIN3-Pad7)") (class "Default")
      (node (ref "U1") (pin "7") (pinfunction "AIN3_7") (pintype "input"))
    )
    (net (code "125") (name "unconnected-(U1-ALERT{slash}RDY-Pad2)") (class "Default")
      (node (ref "U1") (pin "2") (pinfunction "ALERT/RDY_2") (pintype "input"))
    )
  )
)
